# PWR_SMPS_6A_28V.net
KiCad netlist of a schematic drawn in Altium Designer
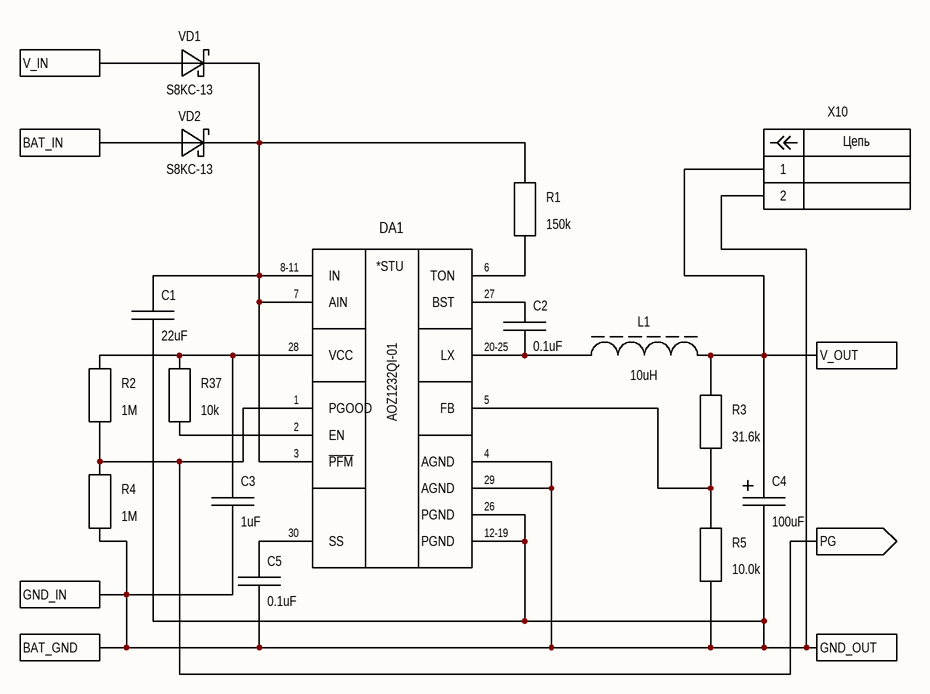
[diagram p0: PWR SMPS 6A 28V.SchDoc]

(export (version "E")
  (design (tool "Eeschema 10.0.6"))
  (components
    (comp (ref "C1")
      (value "22uF")
      (footprint "CAPC2012L")
      (description "Capacitor Ceramic 22uF 25V")
      (fields (field (name "TOLERANCE") "±20%") (field (name "MANUFACTURER") "Yageo"))
      (libsource (lib "Capacitors") (part "CC0805MKX5R8BB226"))
    )
    (comp (ref "C2")
      (value "0.1uF")
      (footprint "CAPC1608L")
      (description "Capacitor Ceramic 0.1uF 25V")
      (fields (field (name "TOLERANCE") "±10%") (field (name "MANUFACTURER") "Yageo"))
      (libsource (lib "Capacitors") (part "CC0603KRX7R8BB104"))
    )
    (comp (ref "C3")
      (value "1uF")
      (footprint "CAPC1608L")
      (description "Capacitor Ceramic 1uF 25V")
      (fields (field (name "TOLERANCE") "±10%") (field (name "MANUFACTURER") "Yageo"))
      (libsource (lib "Capacitors") (part "CC0603KRX5R8BB105"))
    )
    (comp (ref "C4")
      (value "100uF")
      (footprint "CAPA6.3LS")
      (description "Capacitor Aluminum 100uF 25V")
      (fields (field (name "TOLERANCE") "±20%") (field (name "MANUFACTURER") "Nichicon"))
      (libsource (lib "Capacitors") (part "UWT1E101MCL1GS"))
    )
    (comp (ref "C5")
      (value "0.1uF")
      (footprint "CAPC1608L")
      (description "Capacitor Ceramic 0.1uF 25V")
      (fields (field (name "TOLERANCE") "±10%") (field (name "MANUFACTURER") "Yageo"))
      (libsource (lib "Capacitors") (part "CC0603KRX7R8BB104"))
    )
    (comp (ref "DA1")
      (value "AOZ1232QI-01")
      (footprint "QFN-30 (5x5)")
      (description "SWR Down, 6A, 0.1-1MHz, 2.7-28V, 0.8-23.8V")
      (fields (field (name "MANUFACTURER") "Alpha & Omega Semiconductor"))
      (libsource (lib "Power") (part "AOZ1232QI-01"))
    )
    (comp (ref "L1")
      (value "10uH")
      (footprint "INDF12.5x12.5SSH")
      (description "Fixed Inductor 10µH 5.5A")
      (fields (field (name "TOLERANCE") "±30%") (field (name "MANUFACTURER") "Bourns"))
      (libsource (lib "Inductors") (part "SRR1260-100M"))
    )
    (comp (ref "R1")
      (value "150k")
      (footprint "RESC1608L")
      (description "Resistor Ceramic 150k 1608")
      (fields (field (name "MANUFACTURER") "Yageo") (field (name "TOLERANCE") "±5%"))
      (libsource (lib "Resistors") (part "RC0603JR-07150KL"))
    )
    (comp (ref "R2")
      (value "1M")
      (footprint "RESC1608L")
      (description "Resistor Ceramic 1M 1608")
      (fields (field (name "MANUFACTURER") "Yageo") (field (name "TOLERANCE") "±5%"))
      (libsource (lib "Resistors") (part "RC0603JR-071ML"))
    )
    (comp (ref "R3")
      (value "31.6k")
      (footprint "RESC1608L")
      (description "Resistor Ceramic 31.6k 1608 ±1%")
      (fields (field (name "MANUFACTURER") "Yageo") (field (name "TOLERANCE") "±1%"))
      (libsource (lib "Resistors") (part "RC0603FR-0731K6L"))
    )
    (comp (ref "R4")
      (value "1M")
      (footprint "RESC1608L")
      (description "Resistor Ceramic 1M 1608")
      (fields (field (name "MANUFACTURER") "Yageo") (field (name "TOLERANCE") "±5%"))
      (libsource (lib "Resistors") (part "RC0603JR-071ML"))
    )
    (comp (ref "R5")
      (value "10.0k")
      (footprint "RESC1608L")
      (description "Resistor Ceramic 10k 1608 ±1%")
      (fields (field (name "MANUFACTURER") "Yageo") (field (name "TOLERANCE") "±1%"))
      (libsource (lib "Resistors") (part "RC0603FR-0710KL"))
    )
    (comp (ref "R37")
      (value "10k")
      (footprint "RESC1608L")
      (description "Resistor Ceramic 10k 1608")
      (fields (field (name "MANUFACTURER") "Yageo") (field (name "TOLERANCE") "±5%"))
      (libsource (lib "Resistors") (part "RC0603JR-0710KL"))
    )
    (comp (ref "VD1")
      (value "S8KC-13")
      (footprint "DO-214AB")
      (description "Diode Schottky, 8A, 800V")
      (fields (field (name "MANUFACTURER") "ON Semiconductor"))
      (libsource (lib "Discrete components") (part "S8KC-13"))
    )
    (comp (ref "VD2")
      (value "S8KC-13")
      (footprint "DO-214AB")
      (description "Diode Schottky, 8A, 800V")
      (fields (field (name "MANUFACTURER") "ON Semiconductor"))
      (libsource (lib "Discrete components") (part "S8KC-13"))
    )
    (comp (ref "X10")
      (value "B2B-XH-A N.M.")
      (footprint "B2B-XH-A N.M.")
      (description "Header, 2.54, 2p, Top")
      (fields (field (name "MANUFACTURER") "JST Sales America Inc"))
      (libsource (lib "Connectors") (part "B2B-XH-A N.M."))
    )
  )
  (nets
    (net (code "1") (name "/BAT_GND") (class "Default")
      (node (ref "C1") (pin "2") (pinfunction "2_2") (pintype "passive"))
      (node (ref "C3") (pin "2") (pinfunction "2_2") (pintype "passive"))
      (node (ref "C4") (pin "2") (pinfunction "2_2") (pintype "passive"))
      (node (ref "C5") (pin "2") (pinfunction "2_2") (pintype "passive"))
      (node (ref "DA1") (pin "12-19") (pinfunction "PGND_12-19") (pintype "passive"))
      (node (ref "DA1") (pin "26") (pinfunction "PGND_26") (pintype "passive"))
      (node (ref "DA1") (pin "29") (pinfunction "AGND_29") (pintype "passive"))
      (node (ref "DA1") (pin "4") (pinfunction "AGND_4") (pintype "passive"))
      (node (ref "R4") (pin "2") (pinfunction "2_2") (pintype "passive"))
      (node (ref "R5") (pin "2") (pinfunction "2_2") (pintype "passive"))
      (node (ref "X10") (pin "2") (pinfunction "2_2") (pintype "passive"))
    )
    (net (code "2") (name "/BAT_IN") (class "Default")
      (node (ref "VD2") (pin "1") (pinfunction "Anode_1") (pintype "passive"))
    )
    (net (code "3") (name "/PG") (class "Default")
      (node (ref "DA1") (pin "1") (pinfunction "PGOOD_1") (pintype "passive"))
      (node (ref "R2") (pin "2") (pinfunction "2_2") (pintype "passive"))
      (node (ref "R4") (pin "1") (pinfunction "1_1") (pintype "passive"))
    )
    (net (code "4") (name "/V_IN") (class "Default")
      (node (ref "VD1") (pin "1") (pinfunction "Anode_1") (pintype "passive"))
    )
    (net (code "5") (name "/V_OUT") (class "Default")
      (node (ref "C4") (pin "1") (pinfunction "1_1") (pintype "passive"))
      (node (ref "L1") (pin "2") (pinfunction "2_2") (pintype "passive"))
      (node (ref "R3") (pin "1") (pinfunction "1_1") (pintype "passive"))
      (node (ref "X10") (pin "1") (pinfunction "1_1") (pintype "passive"))
    )
    (net (code "6") (name "Net-(DA1-AIN)") (class "Default")
      (node (ref "C1") (pin "1") (pinfunction "1_1") (pintype "passive"))
      (node (ref "DA1") (pin "3") (pinfunction "~{PFM}_3") (pintype "passive"))
      (node (ref "DA1") (pin "7") (pinfunction "AIN_7") (pintype "passive"))
      (node (ref "DA1") (pin "8-11") (pinfunction "IN_8-11") (pintype "passive"))
      (node (ref "R1") (pin "1") (pinfunction "1_1") (pintype "passive"))
      (node (ref "VD1") (pin "2") (pinfunction "Cathode_2") (pintype "passive"))
      (node (ref "VD2") (pin "2") (pinfunction "Cathode_2") (pintype "passive"))
    )
    (net (code "7") (name "Net-(DA1-BST)") (class "Default")
      (node (ref "C2") (pin "1") (pinfunction "1_1") (pintype "passive"))
      (node (ref "DA1") (pin "27") (pinfunction "BST_27") (pintype "passive"))
    )
    (net (code "8") (name "Net-(DA1-EN)") (class "Default")
      (node (ref "DA1") (pin "2") (pinfunction "EN_2") (pintype "passive"))
      (node (ref "R37") (pin "2") (pinfunction "2_2") (pintype "passive"))
    )
    (net (code "9") (name "Net-(DA1-FB)") (class "Default")
      (node (ref "DA1") (pin "5") (pinfunction "FB_5") (pintype "passive"))
      (node (ref "R3") (pin "2") (pinfunction "2_2") (pintype "passive"))
      (node (ref "R5") (pin "1") (pinfunction "1_1") (pintype "passive"))
    )
    (net (code "10") (name "Net-(DA1-LX)") (class "Default")
      (node (ref "C2") (pin "2") (pinfunction "2_2") (pintype "passive"))
      (node (ref "DA1") (pin "20-25") (pinfunction "LX_20-25") (pintype "passive"))
      (node (ref "L1") (pin "1") (pinfunction "1_1") (pintype "passive"))
    )
    (net (code "11") (name "Net-(DA1-SS)") (class "Default")
      (node (ref "C5") (pin "1") (pinfunction "1_1") (pintype "passive"))
      (node (ref "DA1") (pin "30") (pinfunction "SS_30") (pintype "passive"))
    )
    (net (code "12") (name "Net-(DA1-TON)") (class "Default")
      (node (ref "DA1") (pin "6") (pinfunction "TON_6") (pintype "passive"))
      (node (ref "R1") (pin "2") (pinfunction "2_2") (pintype "passive"))
    )
    (net (code "13") (name "Net-(DA1-VCC)") (class "Default")
      (node (ref "C3") (pin "1") (pinfunction "1_1") (pintype "passive"))
      (node (ref "DA1") (pin "28") (pinfunction "VCC_28") (pintype "passive"))
      (node (ref "R2") (pin "1") (pinfunction "1_1") (pintype "passive"))
      (node (ref "R37") (pin "1") (pinfunction "1_1") (pintype "passive"))
    )
  )
)
